# MicrocontrollerV1.net
KiCad netlist of a schematic drawn in EAGLE
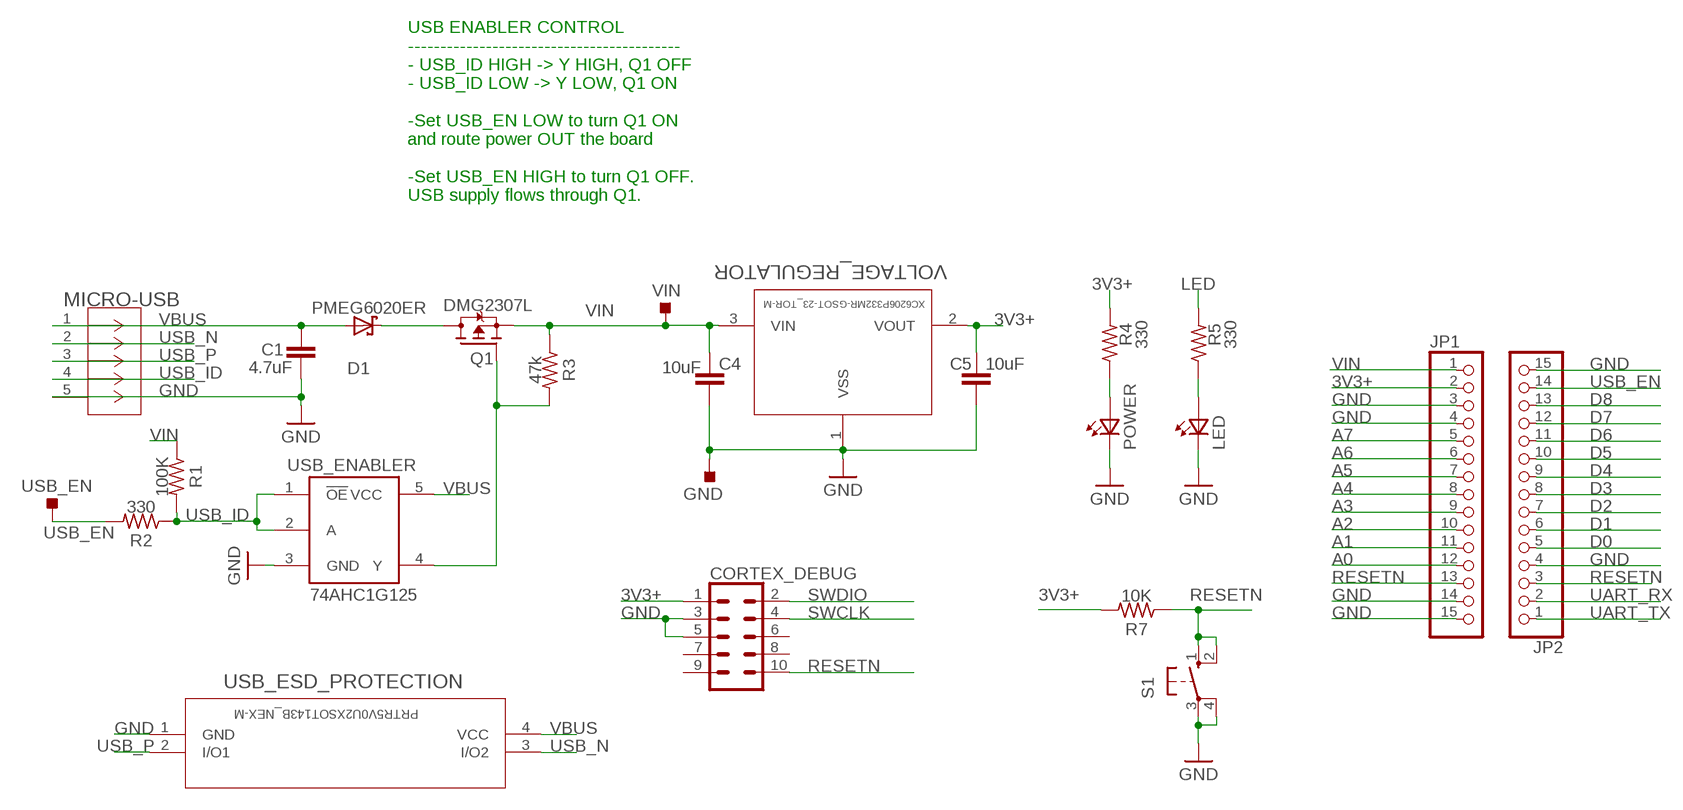
[diagram p0: schematic, sheet 1, part 1 of 2]
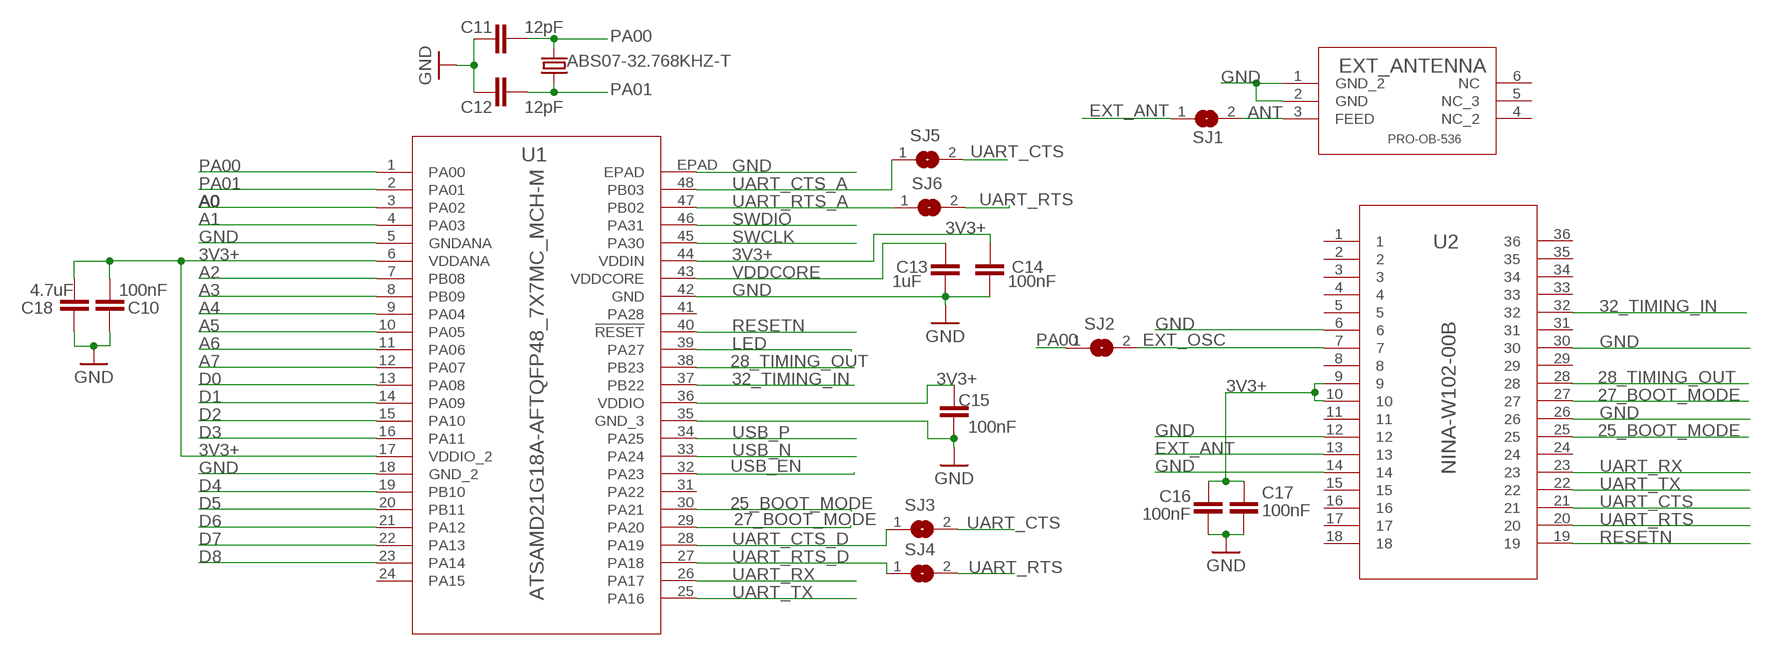
[diagram p1: schematic, sheet 1, part 2 of 2]

(export (version "E")
  (design (tool "Eeschema 10.0.6"))
  (components
    (comp (ref "ABS07-32.768KHZ-T")
      (value "32.768KHz")
      (footprint "eagle-import:ABS07-32.768KHZ-T")
      (fields
        (field (name "DIGIKEY_PART_NUMBER") "535-9542-2-ND")
        (field (name "MANUFACTURER") "Abracon LLC")
        (field (name "MPN") "ABS07-32.768KHZ-T")
        (field (name "CREATED_BY") "PCBLayout.com")
      )
      (libsource (lib "eagle-import") (part "ABS07-32.768KHZ-T"))
    )
    (comp (ref "C1")
      (value "4.7uF")
      (footprint "eagle-import:CAPC1608X85")
      (libsource (lib "eagle-import") (part "CCHIP-0603(1608-METRIC)_"))
    )
    (comp (ref "C4")
      (value "10uF")
      (footprint "eagle-import:CAPC1608X85")
      (libsource (lib "eagle-import") (part "CCHIP-0603(1608-METRIC)_"))
    )
    (comp (ref "C5")
      (value "10uF")
      (footprint "eagle-import:CAPC1608X85")
      (libsource (lib "eagle-import") (part "CCHIP-0603(1608-METRIC)_"))
    )
    (comp (ref "C10")
      (value "100nF")
      (footprint "eagle-import:CAPC1608X85")
      (libsource (lib "eagle-import") (part "CCHIP-0603(1608-METRIC)_"))
    )
    (comp (ref "C11")
      (value "12pF")
      (footprint "eagle-import:CAPC1608X85")
      (libsource (lib "eagle-import") (part "CCHIP-0603(1608-METRIC)_"))
    )
    (comp (ref "C12")
      (value "12pF")
      (footprint "eagle-import:CAPC1608X85")
      (libsource (lib "eagle-import") (part "CCHIP-0603(1608-METRIC)_"))
    )
    (comp (ref "C13")
      (value "1uF")
      (footprint "eagle-import:CAPC1608X85")
      (libsource (lib "eagle-import") (part "CCHIP-0603(1608-METRIC)_"))
    )
    (comp (ref "C14")
      (value "100nF")
      (footprint "eagle-import:CAPC1608X85")
      (libsource (lib "eagle-import") (part "CCHIP-0603(1608-METRIC)_"))
    )
    (comp (ref "C15")
      (value "100nF")
      (footprint "eagle-import:CAPC1608X85")
      (libsource (lib "eagle-import") (part "CCHIP-0603(1608-METRIC)_"))
    )
    (comp (ref "C16")
      (value "100nF")
      (footprint "eagle-import:CAPC1608X85")
      (libsource (lib "eagle-import") (part "CCHIP-0603(1608-METRIC)_"))
    )
    (comp (ref "C17")
      (value "100nF")
      (footprint "eagle-import:CAPC1608X85")
      (libsource (lib "eagle-import") (part "CCHIP-0603(1608-METRIC)_"))
    )
    (comp (ref "C18")
      (value "4.7uF")
      (footprint "eagle-import:CAPC1608X85")
      (libsource (lib "eagle-import") (part "CCHIP-0603(1608-METRIC)_"))
    )
    (comp (ref "CORTEX_DEBUG")
      (value "CONN_05X2NO_SILK")
      (footprint "eagle-import:2X5_NOSILK")
      (libsource (lib "eagle-import") (part "CONN_05X2NO_SILK"))
    )
    (comp (ref "D1")
      (value "PMEG6020ER")
      (footprint "eagle-import:SOD123W")
      (libsource (lib "eagle-import") (part "PMEG6020ER"))
    )
    (comp (ref "EXT_ANTENNA")
      (value "PRO-OB-536")
      (footprint "eagle-import:PRO-OB-536_PAB")
      (fields (field (name "COPYRIGHT") "Copyright (C) 2018 Accelerated Designs. All rights reserved"))
      (libsource (lib "eagle-import") (part "PRO-OB-536"))
    )
    (comp (ref "GND")
      (value "TESTPOINT_TPS-SMD-10SN")
      (footprint "eagle-import:TESTPOINT_SMD-10SN")
      (libsource (lib "eagle-import") (part "TESTPOINT_TPS-SMD-10SN"))
    )
    (comp (ref "JP1")
      (value "PINHD-1X15")
      (footprint "eagle-import:1X15")
      (libsource (lib "eagle-import") (part "PINHD-1X15"))
    )
    (comp (ref "JP2")
      (value "PINHD-1X15")
      (footprint "eagle-import:1X15")
      (libsource (lib "eagle-import") (part "PINHD-1X15"))
    )
    (comp (ref "LED")
      (value "HSMR-C190")
      (footprint "eagle-import:0603")
      (fields (field (name "MF") "Broadcom Limited"))
      (libsource (lib "eagle-import") (part "HSMR-C190"))
    )
    (comp (ref "MICRO-USB")
      (value "ZX62-AB-5PA(31)")
      (footprint "eagle-import:CONN5_ZX62-AB-5PA_HIR")
      (fields (field (name "COPYRIGHT") "Copyright (C) 2016 Accelerated Designs. All rights reserved"))
      (libsource (lib "eagle-import") (part "ZX62-AB-5PA(31)"))
    )
    (comp (ref "POWER")
      (value "HSMR-C190")
      (footprint "eagle-import:0603")
      (fields (field (name "MF") "Broadcom Limited"))
      (libsource (lib "eagle-import") (part "HSMR-C190"))
    )
    (comp (ref "Q1")
      (value "DMG2307L")
      (footprint "eagle-import:SOT96P240X110-3N")
      (fields (field (name "MF") "Diodes Inc."))
      (libsource (lib "eagle-import") (part "DMG2307L"))
    )
    (comp (ref "R1")
      (value "100K")
      (footprint "eagle-import:RESC1608X60")
      (libsource (lib "eagle-import") (part "R-USCHIP-0603(1608-METRIC)_"))
    )
    (comp (ref "R2")
      (value "330")
      (footprint "eagle-import:RESC1608X60")
      (libsource (lib "eagle-import") (part "R-USCHIP-0603(1608-METRIC)_"))
    )
    (comp (ref "R3")
      (value "47k")
      (footprint "eagle-import:RESC1608X60")
      (libsource (lib "eagle-import") (part "R-USCHIP-0603(1608-METRIC)_"))
    )
    (comp (ref "R4")
      (value "330")
      (footprint "eagle-import:RESC1608X60")
      (libsource (lib "eagle-import") (part "R-USCHIP-0603(1608-METRIC)_"))
    )
    (comp (ref "R5")
      (value "330")
      (footprint "eagle-import:RESC1608X60")
      (libsource (lib "eagle-import") (part "R-USCHIP-0603(1608-METRIC)_"))
    )
    (comp (ref "R7")
      (value "10K")
      (footprint "eagle-import:RESC1608X60")
      (libsource (lib "eagle-import") (part "R-USCHIP-0603(1608-METRIC)_"))
    )
    (comp (ref "S1")
      (value "PTS525SK08")
      (footprint "eagle-import:SM08")
      (fields (field (name "MF") "C&K Components") (field (name "MPN") "PTS525SK08SMTRLFS"))
      (libsource (lib "eagle-import") (part "PTS52508SK"))
    )
    (comp (ref "SJ1") (value "SJ") (footprint "eagle-import:SJ") (libsource (lib "eagle-import") (part "SJ")))
    (comp (ref "SJ2") (value "SJ") (footprint "eagle-import:SJ") (libsource (lib "eagle-import") (part "SJ")))
    (comp (ref "SJ3") (value "SJ") (footprint "eagle-import:SJ") (libsource (lib "eagle-import") (part "SJ")))
    (comp (ref "SJ4") (value "SJ") (footprint "eagle-import:SJ") (libsource (lib "eagle-import") (part "SJ")))
    (comp (ref "SJ5") (value "SJ") (footprint "eagle-import:SJ") (libsource (lib "eagle-import") (part "SJ")))
    (comp (ref "SJ6") (value "SJ") (footprint "eagle-import:SJ") (libsource (lib "eagle-import") (part "SJ")))
    (comp (ref "U1")
      (value "ATSAMD21G18A-AFTQFP48_7X7MC_MCH-M")
      (footprint "eagle-import:TQFP48_7X7MC_MCH-M")
      (fields
        (field (name "MANUFACTURER_PART_NUMBER") "ATSAMD21G18A-AF")
        (field (name "COPYRIGHT") "Copyright (C) 2018 Accelerated Designs. All rights reserved")
      )
      (libsource (lib "eagle-import") (part "ATSAMD21G18A-AFTQFP48_7X7MC_MCH-M"))
    )
    (comp (ref "U2")
      (value "NINA-W102-00B")
      (footprint "eagle-import:QFN_W151-00B_UBL")
      (fields (field (name "COPYRIGHT") "Copyright (C) 2018 Accelerated Designs. All rights reserved"))
      (libsource (lib "eagle-import") (part "NINA-W102-00B"))
    )
    (comp (ref "USB_EN")
      (value "TESTPOINT_TPS-SMD-10SN")
      (footprint "eagle-import:TESTPOINT_SMD-10SN")
      (libsource (lib "eagle-import") (part "TESTPOINT_TPS-SMD-10SN"))
    )
    (comp (ref "USB_ENABLER")
      (value "74AHC1G125")
      (footprint "eagle-import:SOT23-5L")
      (fields (field (name "MF") "Texas Instruments"))
      (libsource (lib "eagle-import") (part "74AHC1G125"))
    )
    (comp (ref "USB_ESD_PROTECTION")
      (value "PRTR5V0U2XSOT143B_NEX-M")
      (footprint "eagle-import:SOT143B_NEX-M")
      (fields
        (field (name "MANUFACTURER_PART_NUMBER") "PRTR5V0U2X")
        (field (name "COPYRIGHT") "Copyright (C) 2016 Accelerated Designs. All rights reserved")
      )
      (libsource (lib "eagle-import") (part "PRTR5V0U2XSOT143B_NEX-M"))
    )
    (comp (ref "VIN")
      (value "TESTPOINT_TPS-SMD-10SN")
      (footprint "eagle-import:TESTPOINT_SMD-10SN")
      (libsource (lib "eagle-import") (part "TESTPOINT_TPS-SMD-10SN"))
    )
    (comp (ref "VOLTAGE_REGULATOR")
      (value "XC6206P332MR-GSOT-23_TOR-M")
      (footprint "eagle-import:SOT-23_TOR-M")
      (fields (field (name "MANUFACTURER_PART_NUMBER") "XC6206P332MR-G"))
      (libsource (lib "eagle-import") (part "XC6206P332MR-GSOT-23_TOR-M"))
    )
  )
  (nets
    (net (code "1") (name "/3V3+") (class "Default")
      (node (ref "C10") (pin "2") (pinfunction "2_2") (pintype "passive"))
      (node (ref "C14") (pin "2") (pinfunction "2_2") (pintype "passive"))
      (node (ref "C15") (pin "2") (pinfunction "2_2") (pintype "passive"))
      (node (ref "C16") (pin "1") (pinfunction "1_1") (pintype "passive"))
      (node (ref "C17") (pin "2") (pinfunction "2_2") (pintype "passive"))
      (node (ref "C18") (pin "2") (pinfunction "2_2") (pintype "passive"))
      (node (ref "C5") (pin "1") (pinfunction "1_1") (pintype "passive"))
      (node (ref "CORTEX_DEBUG") (pin "1") (pinfunction "1_1") (pintype "passive"))
      (node (ref "JP1") (pin "2") (pinfunction "2_2") (pintype "passive"))
      (node (ref "R4") (pin "2") (pinfunction "2_2") (pintype "passive"))
      (node (ref "R7") (pin "2") (pinfunction "2_2") (pintype "passive"))
      (node (ref "U1") (pin "17") (pinfunction "VDDIO_2_17") (pintype "power_in"))
      (node (ref "U1") (pin "36") (pinfunction "VDDIO_36") (pintype "power_in"))
      (node (ref "U1") (pin "44") (pinfunction "VDDIN_44") (pintype "power_in"))
      (node (ref "U1") (pin "6") (pinfunction "VDDANA_6") (pintype "power_in"))
      (node (ref "U2") (pin "10") (pinfunction "10_10") (pintype "power_in"))
      (node (ref "U2") (pin "9") (pinfunction "9_9") (pintype "power_in"))
      (node (ref "VOLTAGE_REGULATOR") (pin "2") (pinfunction "VOUT_2") (pintype "output"))
    )
    (net (code "2") (name "/25_BOOT_MODE") (class "Default")
      (node (ref "U1") (pin "30") (pinfunction "PA21_30") (pintype "bidirectional"))
      (node (ref "U2") (pin "25") (pinfunction "25_25") (pintype "passive"))
    )
    (net (code "3") (name "/27_BOOT_MODE") (class "Default")
      (node (ref "U1") (pin "29") (pinfunction "PA20_29") (pintype "bidirectional"))
      (node (ref "U2") (pin "27") (pinfunction "27_27") (pintype "passive"))
    )
    (net (code "4") (name "/28_TIMING_OUT") (class "Default")
      (node (ref "U1") (pin "38") (pinfunction "PB23_38") (pintype "bidirectional"))
      (node (ref "U2") (pin "28") (pinfunction "28_28") (pintype "passive"))
    )
    (net (code "5") (name "/32_TIMING_IN") (class "Default")
      (node (ref "U1") (pin "37") (pinfunction "PB22_37") (pintype "bidirectional"))
      (node (ref "U2") (pin "32") (pinfunction "32_32") (pintype "passive"))
    )
    (net (code "6") (name "/A0") (class "Default")
      (node (ref "JP1") (pin "12") (pinfunction "12_12") (pintype "passive"))
      (node (ref "U1") (pin "3") (pinfunction "PA02_3") (pintype "bidirectional"))
    )
    (net (code "7") (name "/A1") (class "Default")
      (node (ref "JP1") (pin "11") (pinfunction "11_11") (pintype "passive"))
      (node (ref "U1") (pin "4") (pinfunction "PA03_4") (pintype "bidirectional"))
    )
    (net (code "8") (name "/A2") (class "Default")
      (node (ref "JP1") (pin "10") (pinfunction "10_10") (pintype "passive"))
      (node (ref "U1") (pin "7") (pinfunction "PB08_7") (pintype "bidirectional"))
    )
    (net (code "9") (name "/A3") (class "Default")
      (node (ref "JP1") (pin "9") (pinfunction "9_9") (pintype "passive"))
      (node (ref "U1") (pin "8") (pinfunction "PB09_8") (pintype "bidirectional"))
    )
    (net (code "10") (name "/A4") (class "Default")
      (node (ref "JP1") (pin "8") (pinfunction "8_8") (pintype "passive"))
      (node (ref "U1") (pin "9") (pinfunction "PA04_9") (pintype "bidirectional"))
    )
    (net (code "11") (name "/A5") (class "Default")
      (node (ref "JP1") (pin "7") (pinfunction "7_7") (pintype "passive"))
      (node (ref "U1") (pin "10") (pinfunction "PA05_10") (pintype "bidirectional"))
    )
    (net (code "12") (name "/A6") (class "Default")
      (node (ref "JP1") (pin "6") (pinfunction "6_6") (pintype "passive"))
      (node (ref "U1") (pin "11") (pinfunction "PA06_11") (pintype "bidirectional"))
    )
    (net (code "13") (name "/A7") (class "Default")
      (node (ref "JP1") (pin "5") (pinfunction "5_5") (pintype "passive"))
      (node (ref "U1") (pin "12") (pinfunction "PA07_12") (pintype "bidirectional"))
    )
    (net (code "14") (name "/ANT") (class "Default")
      (node (ref "EXT_ANTENNA") (pin "3") (pinfunction "FEED_3") (pintype "passive"))
      (node (ref "SJ1") (pin "2") (pinfunction "2_2") (pintype "passive"))
    )
    (net (code "15") (name "/D0") (class "Default")
      (node (ref "JP2") (pin "5") (pinfunction "5_5") (pintype "passive"))
      (node (ref "U1") (pin "13") (pinfunction "PA08_13") (pintype "bidirectional"))
    )
    (net (code "16") (name "/D1") (class "Default")
      (node (ref "JP2") (pin "6") (pinfunction "6_6") (pintype "passive"))
      (node (ref "U1") (pin "14") (pinfunction "PA09_14") (pintype "bidirectional"))
    )
    (net (code "17") (name "/D2") (class "Default")
      (node (ref "JP2") (pin "7") (pinfunction "7_7") (pintype "passive"))
      (node (ref "U1") (pin "15") (pinfunction "PA10_15") (pintype "bidirectional"))
    )
    (net (code "18") (name "/D3") (class "Default")
      (node (ref "JP2") (pin "8") (pinfunction "8_8") (pintype "passive"))
      (node (ref "U1") (pin "16") (pinfunction "PA11_16") (pintype "bidirectional"))
    )
    (net (code "19") (name "/D4") (class "Default")
      (node (ref "JP2") (pin "9") (pinfunction "9_9") (pintype "passive"))
      (node (ref "U1") (pin "19") (pinfunction "PB10_19") (pintype "bidirectional"))
    )
    (net (code "20") (name "/D5") (class "Default")
      (node (ref "JP2") (pin "10") (pinfunction "10_10") (pintype "passive"))
      (node (ref "U1") (pin "20") (pinfunction "PB11_20") (pintype "bidirectional"))
    )
    (net (code "21") (name "/D6") (class "Default")
      (node (ref "JP2") (pin "11") (pinfunction "11_11") (pintype "passive"))
      (node (ref "U1") (pin "21") (pinfunction "PA12_21") (pintype "bidirectional"))
    )
    (net (code "22") (name "/D7") (class "Default")
      (node (ref "JP2") (pin "12") (pinfunction "12_12") (pintype "passive"))
      (node (ref "U1") (pin "22") (pinfunction "PA13_22") (pintype "bidirectional"))
    )
    (net (code "23") (name "/D8") (class "Default")
      (node (ref "JP2") (pin "13") (pinfunction "13_13") (pintype "passive"))
      (node (ref "U1") (pin "23") (pinfunction "PA14_23") (pintype "bidirectional"))
    )
    (net (code "24") (name "/EXT_ANT") (class "Default")
      (node (ref "SJ1") (pin "1") (pinfunction "1_1") (pintype "passive"))
      (node (ref "U2") (pin "13") (pinfunction "13_13") (pintype "passive"))
    )
    (net (code "25") (name "/EXT_OSC") (class "Default")
      (node (ref "SJ2") (pin "2") (pinfunction "2_2") (pintype "passive"))
      (node (ref "U2") (pin "7") (pinfunction "7_7") (pintype "passive"))
    )
    (net (code "26") (name "/LED") (class "Default")
      (node (ref "R5") (pin "2") (pinfunction "2_2") (pintype "passive"))
      (node (ref "U1") (pin "39") (pinfunction "PA27_39") (pintype "bidirectional"))
    )
    (net (code "27") (name "/PA00") (class "Default")
      (node (ref "ABS07-32.768KHZ-T") (pin "2") (pinfunction "2_2") (pintype "passive"))
      (node (ref "C11") (pin "2") (pinfunction "2_2") (pintype "passive"))
      (node (ref "SJ2") (pin "1") (pinfunction "1_1") (pintype "passive"))
      (node (ref "U1") (pin "1") (pinfunction "PA00_1") (pintype "bidirectional"))
    )
    (net (code "28") (name "/PA01") (class "Default")
      (node (ref "ABS07-32.768KHZ-T") (pin "1") (pinfunction "1_1") (pintype "passive"))
      (node (ref "C12") (pin "2") (pinfunction "2_2") (pintype "passive"))
      (node (ref "U1") (pin "2") (pinfunction "PA01_2") (pintype "bidirectional"))
    )
    (net (code "29") (name "/RESETN") (class "Default")
      (node (ref "CORTEX_DEBUG") (pin "10") (pinfunction "10_10") (pintype "passive"))
      (node (ref "JP1") (pin "13") (pinfunction "13_13") (pintype "passive"))
      (node (ref "JP2") (pin "3") (pinfunction "3_3") (pintype "passive"))
      (node (ref "R7") (pin "1") (pinfunction "1_1") (pintype "passive"))
      (node (ref "S1") (pin "1") (pinfunction "S_1") (pintype "passive"))
      (node (ref "S1") (pin "2") (pinfunction "S1_2") (pintype "passive"))
      (node (ref "U1") (pin "40") (pinfunction "~{RESET}_40") (pintype "passive"))
      (node (ref "U2") (pin "19") (pinfunction "19_19") (pintype "passive"))
    )
    (net (code "30") (name "/SWCLK") (class "Default")
      (node (ref "CORTEX_DEBUG") (pin "4") (pinfunction "4_4") (pintype "passive"))
      (node (ref "U1") (pin "45") (pinfunction "PA30_45") (pintype "bidirectional"))
    )
    (net (code "31") (name "/SWDIO") (class "Default")
      (node (ref "CORTEX_DEBUG") (pin "2") (pinfunction "2_2") (pintype "passive"))
      (node (ref "U1") (pin "46") (pinfunction "PA31_46") (pintype "bidirectional"))
    )
    (net (code "32") (name "/UART_CTS") (class "Default")
      (node (ref "SJ3") (pin "2") (pinfunction "2_2") (pintype "passive"))
      (node (ref "SJ5") (pin "2") (pinfunction "2_2") (pintype "passive"))
      (node (ref "U2") (pin "21") (pinfunction "21_21") (pintype "bidirectional"))
    )
    (net (code "33") (name "/UART_CTS_A") (class "Default")
      (node (ref "SJ5") (pin "1") (pinfunction "1_1") (pintype "passive"))
      (node (ref "U1") (pin "48") (pinfunction "PB03_48") (pintype "bidirectional"))
    )
    (net (code "34") (name "/UART_CTS_D") (class "Default")
      (node (ref "SJ3") (pin "1") (pinfunction "1_1") (pintype "passive"))
      (node (ref "U1") (pin "28") (pinfunction "PA19_28") (pintype "bidirectional"))
    )
    (net (code "35") (name "/UART_RTS") (class "Default")
      (node (ref "SJ4") (pin "2") (pinfunction "2_2") (pintype "passive"))
      (node (ref "SJ6") (pin "2") (pinfunction "2_2") (pintype "passive"))
      (node (ref "U2") (pin "20") (pinfunction "20_20") (pintype "bidirectional"))
    )
    (net (code "36") (name "/UART_RTS_A") (class "Default")
      (node (ref "SJ6") (pin "1") (pinfunction "1_1") (pintype "passive"))
      (node (ref "U1") (pin "47") (pinfunction "PB02_47") (pintype "bidirectional"))
    )
    (net (code "37") (name "/UART_RTS_D") (class "Default")
      (node (ref "SJ4") (pin "1") (pinfunction "1_1") (pintype "passive"))
      (node (ref "U1") (pin "27") (pinfunction "PA18_27") (pintype "bidirectional"))
    )
    (net (code "38") (name "/UART_RX") (class "Default")
      (node (ref "JP2") (pin "2") (pinfunction "2_2") (pintype "passive"))
      (node (ref "U1") (pin "26") (pinfunction "PA17_26") (pintype "bidirectional"))
      (node (ref "U2") (pin "23") (pinfunction "23_23") (pintype "passive"))
    )
    (net (code "39") (name "/UART_TX") (class "Default")
      (node (ref "JP2") (pin "1") (pinfunction "1_1") (pintype "passive"))
      (node (ref "U1") (pin "25") (pinfunction "PA16_25") (pintype "bidirectional"))
      (node (ref "U2") (pin "22") (pinfunction "22_22") (pintype "passive"))
    )
    (net (code "40") (name "/USB_EN") (class "Default")
      (node (ref "JP2") (pin "14") (pinfunction "14_14") (pintype "passive"))
      (node (ref "R2") (pin "2") (pinfunction "2_2") (pintype "passive"))
      (node (ref "U1") (pin "32") (pinfunction "PA23_32") (pintype "bidirectional"))
      (node (ref "USB_EN") (pin "TP") (pinfunction "TP_TP") (pintype "passive"))
    )
    (net (code "41") (name "/USB_ID") (class "Default")
      (node (ref "MICRO-USB") (pin "4") (pinfunction "4_4") (pintype "passive"))
      (node (ref "R1") (pin "2") (pinfunction "2_2") (pintype "passive"))
      (node (ref "R2") (pin "1") (pinfunction "1_1") (pintype "passive"))
      (node (ref "USB_ENABLER") (pin "1") (pinfunction "~{OE}_1") (pintype "input"))
      (node (ref "USB_ENABLER") (pin "2") (pinfunction "A_2") (pintype "input"))
    )
    (net (code "42") (name "/USB_N") (class "Default")
      (node (ref "MICRO-USB") (pin "2") (pinfunction "2_2") (pintype "passive"))
      (node (ref "U1") (pin "33") (pinfunction "PA24_33") (pintype "bidirectional"))
      (node (ref "USB_ESD_PROTECTION") (pin "3") (pinfunction "I/O2_3") (pintype "passive"))
    )
    (net (code "43") (name "/USB_P") (class "Default")
      (node (ref "MICRO-USB") (pin "3") (pinfunction "3_3") (pintype "passive"))
      (node (ref "U1") (pin "34") (pinfunction "PA25_34") (pintype "bidirectional"))
      (node (ref "USB_ESD_PROTECTION") (pin "2") (pinfunction "I/O1_2") (pintype "passive"))
    )
    (net (code "44") (name "/VBUS") (class "Default")
      (node (ref "C1") (pin "1") (pinfunction "1_1") (pintype "passive"))
      (node (ref "D1") (pin "2") (pinfunction "A_2") (pintype "passive"))
      (node (ref "MICRO-USB") (pin "1") (pinfunction "1_1") (pintype "passive"))
      (node (ref "USB_ENABLER") (pin "5") (pinfunction "VCC_5") (pintype "power_in"))
      (node (ref "USB_ESD_PROTECTION") (pin "4") (pinfunction "VCC_4") (pintype "passive"))
    )
    (net (code "45") (name "/VDDCORE") (class "Default")
      (node (ref "C13") (pin "2") (pinfunction "2_2") (pintype "passive"))
      (node (ref "U1") (pin "43") (pinfunction "VDDCORE_43") (pintype "power_in"))
    )
    (net (code "46") (name "/VIN") (class "Default")
      (node (ref "C4") (pin "2") (pinfunction "2_2") (pintype "passive"))
      (node (ref "JP1") (pin "1") (pinfunction "1_1") (pintype "passive"))
      (node (ref "Q1") (pin "2") (pinfunction "S_2") (pintype "passive"))
      (node (ref "R1") (pin "1") (pinfunction "1_1") (pintype "passive"))
      (node (ref "R3") (pin "1") (pinfunction "1_1") (pintype "passive"))
      (node (ref "VIN") (pin "TP") (pinfunction "TP_TP") (pintype "passive"))
      (node (ref "VOLTAGE_REGULATOR") (pin "3") (pinfunction "VIN_3") (pintype "power_in"))
    )
    (net (code "47") (name "GND") (class "Default")
      (node (ref "C1") (pin "2") (pinfunction "2_2") (pintype "passive"))
      (node (ref "C10") (pin "1") (pinfunction "1_1") (pintype "passive"))
      (node (ref "C11") (pin "1") (pinfunction "1_1") (pintype "passive"))
      (node (ref "C12") (pin "1") (pinfunction "1_1") (pintype "passive"))
      (node (ref "C13") (pin "1") (pinfunction "1_1") (pintype "passive"))
      (node (ref "C14") (pin "1") (pinfunction "1_1") (pintype "passive"))
      (node (ref "C15") (pin "1") (pinfunction "1_1") (pintype "passive"))
      (node (ref "C16") (pin "2") (pinfunction "2_2") (pintype "passive"))
      (node (ref "C17") (pin "1") (pinfunction "1_1") (pintype "passive"))
      (node (ref "C18") (pin "1") (pinfunction "1_1") (pintype "passive"))
      (node (ref "C4") (pin "1") (pinfunction "1_1") (pintype "passive"))
      (node (ref "C5") (pin "2") (pinfunction "2_2") (pintype "passive"))
      (node (ref "CORTEX_DEBUG") (pin "3") (pinfunction "3_3") (pintype "passive"))
      (node (ref "CORTEX_DEBUG") (pin "5") (pinfunction "5_5") (pintype "passive"))
      (node (ref "EXT_ANTENNA") (pin "1") (pinfunction "GND_2_1") (pintype "passive"))
      (node (ref "EXT_ANTENNA") (pin "2") (pinfunction "GND_2") (pintype "passive"))
      (node (ref "GND") (pin "TP") (pinfunction "TP_TP") (pintype "passive"))
      (node (ref "JP1") (pin "14") (pinfunction "14_14") (pintype "passive"))
      (node (ref "JP1") (pin "15") (pinfunction "15_15") (pintype "passive"))
      (node (ref "JP1") (pin "3") (pinfunction "3_3") (pintype "passive"))
      (node (ref "JP1") (pin "4") (pinfunction "4_4") (pintype "passive"))
      (node (ref "JP2") (pin "15") (pinfunction "15_15") (pintype "passive"))
      (node (ref "JP2") (pin "4") (pinfunction "4_4") (pintype "passive"))
      (node (ref "LED") (pin "1") (pinfunction "K2_1") (pintype "passive"))
      (node (ref "MICRO-USB") (pin "5") (pinfunction "5_5") (pintype "passive"))
      (node (ref "POWER") (pin "1") (pinfunction "K2_1") (pintype "passive"))
      (node (ref "S1") (pin "3") (pinfunction "P_3") (pintype "passive"))
      (node (ref "S1") (pin "4") (pinfunction "P1_4") (pintype "passive"))
      (node (ref "U1") (pin "18") (pinfunction "GND_2_18") (pintype "passive"))
      (node (ref "U1") (pin "35") (pinfunction "GND_3_35") (pintype "passive"))
      (node (ref "U1") (pin "42") (pinfunction "GND_42") (pintype "passive"))
      (node (ref "U1") (pin "5") (pinfunction "GNDANA_5") (pintype "passive"))
      (node (ref "U1") (pin "EPAD") (pinfunction "EPAD_EPAD") (pintype "passive"))
      (node (ref "U2") (pin "12") (pinfunction "12_12") (pintype "passive"))
      (node (ref "U2") (pin "14") (pinfunction "14_14") (pintype "passive"))
      (node (ref "U2") (pin "26") (pinfunction "26_26") (pintype "passive"))
      (node (ref "U2") (pin "30") (pinfunction "30_30") (pintype "passive"))
      (node (ref "U2") (pin "6") (pinfunction "6_6") (pintype "passive"))
      (node (ref "USB_ENABLER") (pin "3") (pinfunction "GND_3") (pintype "power_in"))
      (node (ref "USB_ESD_PROTECTION") (pin "1") (pinfunction "GND_1") (pintype "passive"))
      (node (ref "VOLTAGE_REGULATOR") (pin "1") (pinfunction "VSS_1") (pintype "passive"))
    )
    (net (code "48") (name "Net-(D1-K)") (class "Default")
      (node (ref "D1") (pin "1") (pinfunction "K_1") (pintype "passive"))
      (node (ref "Q1") (pin "3") (pinfunction "D_3") (pintype "passive"))
    )
    (net (code "49") (name "Net-(LED-A2)") (class "Default")
      (node (ref "LED") (pin "2") (pinfunction "A2_2") (pintype "passive"))
      (node (ref "R5") (pin "1") (pinfunction "1_1") (pintype "passive"))
    )
    (net (code "50") (name "Net-(POWER-A2)") (class "Default")
      (node (ref "POWER") (pin "2") (pinfunction "A2_2") (pintype "passive"))
      (node (ref "R4") (pin "1") (pinfunction "1_1") (pintype "passive"))
    )
    (net (code "51") (name "Net-(Q1-G)") (class "Default")
      (node (ref "Q1") (pin "1") (pinfunction "G_1") (pintype "passive"))
      (node (ref "R3") (pin "2") (pinfunction "2_2") (pintype "passive"))
      (node (ref "USB_ENABLER") (pin "4") (pinfunction "Y_4") (pintype "output"))
    )
    (net (code "52") (name "unconnected-(CORTEX_DEBUG-Pad6)") (class "Default")
      (node (ref "CORTEX_DEBUG") (pin "6") (pinfunction "6_6") (pintype "passive"))
    )
    (net (code "53") (name "unconnected-(CORTEX_DEBUG-Pad7)") (class "Default")
      (node (ref "CORTEX_DEBUG") (pin "7") (pinfunction "7_7") (pintype "passive"))
    )
    (net (code "54") (name "unconnected-(CORTEX_DEBUG-Pad8)") (class "Default")
      (node (ref "CORTEX_DEBUG") (pin "8") (pinfunction "8_8") (pintype "passive"))
    )
    (net (code "55") (name "unconnected-(CORTEX_DEBUG-Pad9)") (class "Default")
      (node (ref "CORTEX_DEBUG") (pin "9") (pinfunction "9_9") (pintype "passive"))
    )
    (net (code "56") (name "unconnected-(EXT_ANTENNA-NC-Pad6)") (class "Default")
      (node (ref "EXT_ANTENNA") (pin "6") (pinfunction "NC_6") (pintype "no_connect"))
    )
    (net (code "57") (name "unconnected-(EXT_ANTENNA-NC_2-Pad4)") (class "Default")
      (node (ref "EXT_ANTENNA") (pin "4") (pinfunction "NC_2_4") (pintype "no_connect"))
    )
    (net (code "58") (name "unconnected-(EXT_ANTENNA-NC_3-Pad5)") (class "Default")
      (node (ref "EXT_ANTENNA") (pin "5") (pinfunction "NC_3_5") (pintype "no_connect"))
    )
    (net (code "59") (name "unconnected-(U1-PA15-Pad24)") (class "Default")
      (node (ref "U1") (pin "24") (pinfunction "PA15_24") (pintype "bidirectional"))
    )
    (net (code "60") (name "unconnected-(U1-PA22-Pad31)") (class "Default")
      (node (ref "U1") (pin "31") (pinfunction "PA22_31") (pintype "bidirectional"))
    )
    (net (code "61") (name "unconnected-(U1-PA28-Pad41)") (class "Default")
      (node (ref "U1") (pin "41") (pinfunction "PA28_41") (pintype "bidirectional"))
    )
    (net (code "62") (name "unconnected-(U2-Pad1)") (class "Default")
      (node (ref "U2") (pin "1") (pinfunction "1_1") (pintype "passive"))
    )
    (net (code "63") (name "unconnected-(U2-Pad2)") (class "Default")
      (node (ref "U2") (pin "2") (pinfunction "2_2") (pintype "passive"))
    )
    (net (code "64") (name "unconnected-(U2-Pad3)") (class "Default")
      (node (ref "U2") (pin "3") (pinfunction "3_3") (pintype "passive"))
    )
    (net (code "65") (name "unconnected-(U2-Pad4)") (class "Default")
      (node (ref "U2") (pin "4") (pinfunction "4_4") (pintype "passive"))
    )
    (net (code "66") (name "unconnected-(U2-Pad5)") (class "Default")
      (node (ref "U2") (pin "5") (pinfunction "5_5") (pintype "passive"))
    )
    (net (code "67") (name "unconnected-(U2-Pad8)") (class "Default")
      (node (ref "U2") (pin "8") (pinfunction "8_8") (pintype "passive"))
    )
    (net (code "68") (name "unconnected-(U2-Pad11)") (class "Default")
      (node (ref "U2") (pin "11") (pinfunction "11_11") (pintype "passive"))
    )
    (net (code "69") (name "unconnected-(U2-Pad15)") (class "Default")
      (node (ref "U2") (pin "15") (pinfunction "15_15") (pintype "passive"))
    )
    (net (code "70") (name "unconnected-(U2-Pad16)") (class "Default")
      (node (ref "U2") (pin "16") (pinfunction "16_16") (pintype "bidirectional"))
    )
    (net (code "71") (name "unconnected-(U2-Pad17)") (class "Default")
      (node (ref "U2") (pin "17") (pinfunction "17_17") (pintype "bidirectional"))
    )
    (net (code "72") (name "unconnected-(U2-Pad18)") (class "Default")
      (node (ref "U2") (pin "18") (pinfunction "18_18") (pintype "passive"))
    )
    (net (code "73") (name "unconnected-(U2-Pad24)") (class "Default")
      (node (ref "U2") (pin "24") (pinfunction "24_24") (pintype "passive"))
    )
    (net (code "74") (name "unconnected-(U2-Pad29)") (class "Default")
      (node (ref "U2") (pin "29") (pinfunction "29_29") (pintype "passive"))
    )
    (net (code "75") (name "unconnected-(U2-Pad31)") (class "Default")
      (node (ref "U2") (pin "31") (pinfunction "31_31") (pintype "passive"))
    )
    (net (code "76") (name "unconnected-(U2-Pad33)") (class "Default")
      (node (ref "U2") (pin "33") (pinfunction "33_33") (pintype "passive"))
    )
    (net (code "77") (name "unconnected-(U2-Pad34)") (class "Default")
      (node (ref "U2") (pin "34") (pinfunction "34_34") (pintype "passive"))
    )
    (net (code "78") (name "unconnected-(U2-Pad35)") (class "Default")
      (node (ref "U2") (pin "35") (pinfunction "35_35") (pintype "passive"))
    )
    (net (code "79") (name "unconnected-(U2-Pad36)") (class "Default")
      (node (ref "U2") (pin "36") (pinfunction "36_36") (pintype "passive"))
    )
  )
)
